# Supply_5V_ISOL.net
KiCad netlist of a schematic drawn in Altium Designer
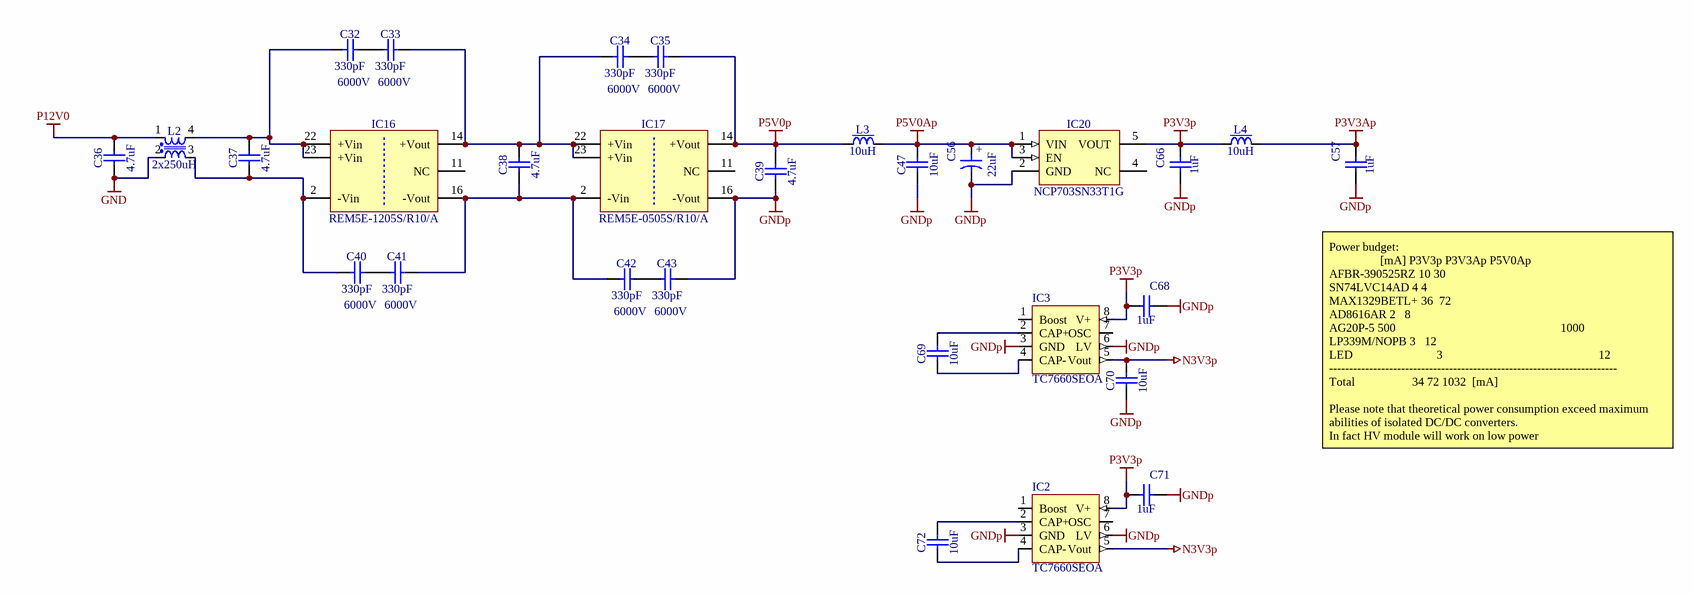
[diagram p0: Supply_5V_ISOL.SchDoc]

(export (version "E")
  (design (tool "Eeschema 10.0.6"))
  (components
    (comp (ref "C32")
      (value "330pF")
      (footprint "CAPC4620X220N")
      (description "Non-polarised capacitor")
      (fields
        (field (name "PART NUMBER") "CC1808_330pF_6000V_10%_X7R_VISHAY_HV")
        (field (name "VOLTAGE") "6000V")
        (field (name "TOLERANCE") "±10%")
        (field (name "AUTHOR") "CERN DEM HF")
      )
      (libsource (lib "Capacitors") (part "Capacitor - non polarized"))
    )
    (comp (ref "C33")
      (value "330pF")
      (footprint "CAPC4620X220N")
      (description "Non-polarised capacitor")
      (fields
        (field (name "PART NUMBER") "CC1808_330pF_6000V_10%_X7R_VISHAY_HV")
        (field (name "VOLTAGE") "6000V")
        (field (name "TOLERANCE") "±10%")
        (field (name "AUTHOR") "CERN DEM HF")
      )
      (libsource (lib "Capacitors") (part "Capacitor - non polarized"))
    )
    (comp (ref "C34")
      (value "330pF")
      (footprint "CAPC4620X220N")
      (description "Non-polarised capacitor")
      (fields
        (field (name "PART NUMBER") "CC1808_330pF_6000V_10%_X7R_VISHAY_HV")
        (field (name "VOLTAGE") "6000V")
        (field (name "TOLERANCE") "±10%")
        (field (name "AUTHOR") "CERN DEM HF")
      )
      (libsource (lib "Capacitors") (part "Capacitor - non polarized"))
    )
    (comp (ref "C35")
      (value "330pF")
      (footprint "CAPC4620X220N")
      (description "Non-polarised capacitor")
      (fields
        (field (name "PART NUMBER") "CC1808_330pF_6000V_10%_X7R_VISHAY_HV")
        (field (name "VOLTAGE") "6000V")
        (field (name "TOLERANCE") "±10%")
        (field (name "AUTHOR") "CERN DEM HF")
      )
      (libsource (lib "Capacitors") (part "Capacitor - non polarized"))
    )
    (comp (ref "C36")
      (value "4.7uF")
      (footprint "CAPC2012X145N")
      (description "Non-polarised capacitor")
      (fields
        (field (name "PART NUMBER") "CC0805_4.7UF_50V_10%_X7R")
        (field (name "VOLTAGE") "50V")
        (field (name "AUTHOR") "CERN DEM JMW")
      )
      (libsource (lib "Capacitors") (part "Capacitor - non polarized"))
    )
    (comp (ref "C37")
      (value "4.7uF")
      (footprint "CAPC2012X145N")
      (description "Non-polarised capacitor")
      (fields
        (field (name "PART NUMBER") "CC0805_4.7UF_50V_10%_X7R")
        (field (name "VOLTAGE") "50V")
        (field (name "AUTHOR") "CERN DEM JMW")
      )
      (libsource (lib "Capacitors") (part "Capacitor - non polarized"))
    )
    (comp (ref "C38")
      (value "4.7uF")
      (footprint "CAPC2012X145N")
      (description "Non-polarised capacitor")
      (fields
        (field (name "PART NUMBER") "CC0805_4.7UF_50V_10%_X7R")
        (field (name "VOLTAGE") "50V")
        (field (name "AUTHOR") "CERN DEM JMW")
      )
      (libsource (lib "Capacitors") (part "Capacitor - non polarized"))
    )
    (comp (ref "C39")
      (value "4.7uF")
      (footprint "CAPC2012X145N")
      (description "Non-polarised capacitor")
      (fields
        (field (name "PART NUMBER") "CC0805_4.7UF_50V_10%_X7R")
        (field (name "VOLTAGE") "50V")
        (field (name "AUTHOR") "CERN DEM JMW")
      )
      (libsource (lib "Capacitors") (part "Capacitor - non polarized"))
    )
    (comp (ref "C40")
      (value "330pF")
      (footprint "CAPC4620X220N")
      (description "Non-polarised capacitor")
      (fields
        (field (name "PART NUMBER") "CC1808_330pF_6000V_10%_X7R_VISHAY_HV")
        (field (name "VOLTAGE") "6000V")
        (field (name "TOLERANCE") "±10%")
        (field (name "AUTHOR") "CERN DEM HF")
      )
      (libsource (lib "Capacitors") (part "Capacitor - non polarized"))
    )
    (comp (ref "C41")
      (value "330pF")
      (footprint "CAPC4620X220N")
      (description "Non-polarised capacitor")
      (fields
        (field (name "PART NUMBER") "CC1808_330pF_6000V_10%_X7R_VISHAY_HV")
        (field (name "VOLTAGE") "6000V")
        (field (name "TOLERANCE") "±10%")
        (field (name "AUTHOR") "CERN DEM HF")
      )
      (libsource (lib "Capacitors") (part "Capacitor - non polarized"))
    )
    (comp (ref "C42")
      (value "330pF")
      (footprint "CAPC4620X220N")
      (description "Non-polarised capacitor")
      (fields
        (field (name "PART NUMBER") "CC1808_330pF_6000V_10%_X7R_VISHAY_HV")
        (field (name "VOLTAGE") "6000V")
        (field (name "TOLERANCE") "±10%")
        (field (name "AUTHOR") "CERN DEM HF")
      )
      (libsource (lib "Capacitors") (part "Capacitor - non polarized"))
    )
    (comp (ref "C43")
      (value "330pF")
      (footprint "CAPC4620X220N")
      (description "Non-polarised capacitor")
      (fields
        (field (name "PART NUMBER") "CC1808_330pF_6000V_10%_X7R_VISHAY_HV")
        (field (name "VOLTAGE") "6000V")
        (field (name "TOLERANCE") "±10%")
        (field (name "AUTHOR") "CERN DEM HF")
      )
      (libsource (lib "Capacitors") (part "Capacitor - non polarized"))
    )
    (comp (ref "C47")
      (value "10uF")
      (footprint "CAPC1608X80N")
      (description "Non-polarised capacitor")
      (fields
        (field (name "PART NUMBER") "CC0603_10UF_16V_20%_X5R")
        (field (name "VOLTAGE") "16V")
        (field (name "AUTHOR") "CERN DEM MR")
      )
      (libsource (lib "Capacitors") (part "Capacitor - non polarized"))
    )
    (comp (ref "C56")
      (value "22uF")
      (footprint "CAPMP3528X210N")
      (description "Polarised capacitor")
      (fields
        (field (name "PART NUMBER") "CTE3528-21_22UF_20V_10%")
        (field (name "VOLTAGE") "20V")
        (field (name "AUTHOR") "CERN DEM JLC")
      )
      (libsource (lib "Capacitors") (part "Capacitor - polarized"))
    )
    (comp (ref "C57")
      (value "1uF")
      (footprint "CAPC1005X55N")
      (description "Non-polarised capacitor")
      (fields
        (field (name "PART NUMBER") "CC0402_1UF_16V_10%_X5R")
        (field (name "VOLTAGE") "16V")
        (field (name "AUTHOR") "CERN DEM JLC")
      )
      (libsource (lib "Capacitors") (part "Capacitor - non polarized"))
    )
    (comp (ref "C66")
      (value "1uF")
      (footprint "CAPC1005X55N")
      (description "Non-polarised capacitor")
      (fields
        (field (name "PART NUMBER") "CC0402_1UF_16V_10%_X5R")
        (field (name "VOLTAGE") "16V")
        (field (name "AUTHOR") "CERN DEM JLC")
      )
      (libsource (lib "Capacitors") (part "Capacitor - non polarized"))
    )
    (comp (ref "C68")
      (value "1uF")
      (footprint "CAPC1005X55N")
      (description "Non-polarised capacitor")
      (fields
        (field (name "PART NUMBER") "CC0402_1UF_16V_10%_X5R")
        (field (name "VOLTAGE") "16V")
        (field (name "AUTHOR") "CERN DEM JLC")
      )
      (libsource (lib "Capacitors") (part "Capacitor - non polarized"))
    )
    (comp (ref "C69")
      (value "10uF")
      (footprint "CAPC1608X80N")
      (description "Non-polarised capacitor")
      (fields
        (field (name "PART NUMBER") "CC0603_10UF_16V_20%_X5R")
        (field (name "VOLTAGE") "16V")
        (field (name "AUTHOR") "CERN DEM MR")
      )
      (libsource (lib "Capacitors") (part "Capacitor - non polarized"))
    )
    (comp (ref "C70")
      (value "10uF")
      (footprint "CAPC1608X80N")
      (description "Non-polarised capacitor")
      (fields
        (field (name "PART NUMBER") "CC0603_10UF_16V_20%_X5R")
        (field (name "VOLTAGE") "16V")
        (field (name "AUTHOR") "CERN DEM MR")
      )
      (libsource (lib "Capacitors") (part "Capacitor - non polarized"))
    )
    (comp (ref "C71")
      (value "1uF")
      (footprint "CAPC1005X55N")
      (description "Non-polarised capacitor")
      (fields
        (field (name "PART NUMBER") "CC0402_1UF_16V_10%_X5R")
        (field (name "VOLTAGE") "16V")
        (field (name "AUTHOR") "CERN DEM JLC")
      )
      (libsource (lib "Capacitors") (part "Capacitor - non polarized"))
    )
    (comp (ref "C72")
      (value "10uF")
      (footprint "CAPC1608X80N")
      (description "Non-polarised capacitor")
      (fields
        (field (name "PART NUMBER") "CC0603_10UF_16V_20%_X5R")
        (field (name "VOLTAGE") "16V")
        (field (name "AUTHOR") "CERN DEM MR")
      )
      (libsource (lib "Capacitors") (part "Capacitor - non polarized"))
    )
    (comp (ref "IC2")
      (value "TC7660SEOA")
      (footprint "SO-8")
      (description "20mA PUMP DC-TO-DC VOLTAGE CONVERTER")
      (libsource (lib "LIBRARY_SCH") (part "PM_TC7660"))
    )
    (comp (ref "IC3")
      (value "TC7660SEOA")
      (footprint "SO-8")
      (description "20mA PUMP DC-TO-DC VOLTAGE CONVERTER")
      (libsource (lib "LIBRARY_SCH") (part "PM_TC7660"))
    )
    (comp (ref "IC16")
      (value "REM5E-1205S/R10/A")
      (footprint "DCDC_RECOM_REM5E-XXXXS")
      (description "RECOM, RP Series, Single Output DCDC Converter")
      (fields (field (name "MANUFACTURER") "RECOM") (field (name "AUTHOR") "CERN DEM HF"))
      (libsource (lib "ICs And Semiconductors") (part "DCDC_RECOM_REM5E-XXXXS"))
    )
    (comp (ref "IC17")
      (value "REM5E-0505S/R10/A")
      (footprint "DCDC_RECOM_REM5E-XXXXS")
      (description "RECOM, RP Series, Single Output DCDC Converter")
      (fields (field (name "MANUFACTURER") "RECOM") (field (name "AUTHOR") "CERN DEM HF"))
      (libsource (lib "ICs And Semiconductors") (part "DCDC_RECOM_REM5E-XXXXS"))
    )
    (comp (ref "IC20")
      (value "NCP703SN33T1G")
      (footprint "SOT95P275X110-5N")
      (description "3.3V 300mA, Ultra-Low Quiescent Current, IQ 12uA, Ultra-Low Noise, LDO Voltage Regulator")
      (fields (field (name "MANUFACTURER") "ON SEMICONDUCTOR") (field (name "AUTHOR") "CERN DEM JLC"))
      (libsource (lib "ICs And Semiconductors") (part "NCP703SN"))
    )
    (comp (ref "L2")
      (value "2x250uH")
      (footprint "IND_WURTH_WE-SL2")
      (description "Inductor Common Mode")
      (fields
        (field (name "PART NUMBER") "IND_250UH_50%_WURTH_WE-SL2-744224")
        (field (name "POWER") "1.2A")
        (field (name "AUTHOR") "CERN DEM JLC")
      )
      (libsource (lib "Inductors & Transformers") (part "Inductor Common Mode 1Dot-4 2Dot-3"))
    )
    (comp (ref "L3")
      (value "10uH")
      (footprint "IND_BOURNS_PM43")
      (description "Inductor With Core")
      (fields
        (field (name "PART NUMBER") "IND_10UH_20%_BOURNS_PM43")
        (field (name "POWER") "1.15A")
        (field (name "AUTHOR") "CERN DEM JLC")
      )
      (libsource (lib "Inductors & Transformers") (part "Inductor With Magnetic core"))
    )
    (comp (ref "L4")
      (value "10uH")
      (footprint "IND_BOURNS_PM43")
      (description "Inductor With Core")
      (fields
        (field (name "PART NUMBER") "IND_10UH_20%_BOURNS_PM43")
        (field (name "POWER") "1.15A")
        (field (name "AUTHOR") "CERN DEM JLC")
      )
      (libsource (lib "Inductors & Transformers") (part "Inductor With Magnetic core"))
    )
  )
  (nets
    (net (code "1") (name "GND") (class "Default")
      (node (ref "C36") (pin "1") (pinfunction "1_1") (pintype "passive"))
      (node (ref "L2") (pin "2") (pinfunction "2_2") (pintype "passive"))
    )
    (net (code "2") (name "GNDp") (class "Default")
      (node (ref "C39") (pin "1") (pinfunction "1_1") (pintype "passive"))
      (node (ref "C43") (pin "2") (pinfunction "2_2") (pintype "passive"))
      (node (ref "C47") (pin "1") (pinfunction "1_1") (pintype "passive"))
      (node (ref "C56") (pin "2") (pinfunction "2_2") (pintype "passive"))
      (node (ref "C57") (pin "1") (pinfunction "1_1") (pintype "passive"))
      (node (ref "C66") (pin "1") (pinfunction "1_1") (pintype "passive"))
      (node (ref "C68") (pin "2") (pinfunction "2_2") (pintype "passive"))
      (node (ref "C70") (pin "1") (pinfunction "1_1") (pintype "passive"))
      (node (ref "C71") (pin "2") (pinfunction "2_2") (pintype "passive"))
      (node (ref "IC17") (pin "16") (pinfunction "-Vout_16") (pintype "power_in"))
      (node (ref "IC2") (pin "3") (pinfunction "GND_3") (pintype "power_in"))
      (node (ref "IC2") (pin "6") (pinfunction "LV_6") (pintype "output"))
      (node (ref "IC20") (pin "2") (pinfunction "GND_2") (pintype "power_in"))
      (node (ref "IC3") (pin "3") (pinfunction "GND_3") (pintype "power_in"))
      (node (ref "IC3") (pin "6") (pinfunction "LV_6") (pintype "output"))
    )
    (net (code "3") (name "N3V3p") (class "Default")
      (node (ref "C70") (pin "2") (pinfunction "2_2") (pintype "passive"))
      (node (ref "IC2") (pin "5") (pinfunction "Vout_5") (pintype "output"))
      (node (ref "IC3") (pin "5") (pinfunction "Vout_5") (pintype "output"))
    )
    (net (code "4") (name "Net-(C32-Pad1)") (class "Default")
      (node (ref "C32") (pin "1") (pinfunction "1_1") (pintype "passive"))
      (node (ref "C37") (pin "2") (pinfunction "2_2") (pintype "passive"))
      (node (ref "IC16") (pin "22") (pinfunction "+Vin_22") (pintype "power_in"))
      (node (ref "IC16") (pin "23") (pinfunction "+Vin_23") (pintype "power_in"))
      (node (ref "L2") (pin "4") (pinfunction "4_4") (pintype "passive"))
    )
    (net (code "5") (name "Net-(C32-Pad2)") (class "Default")
      (node (ref "C32") (pin "2") (pinfunction "2_2") (pintype "passive"))
      (node (ref "C33") (pin "1") (pinfunction "1_1") (pintype "passive"))
    )
    (net (code "6") (name "Net-(C34-Pad2)") (class "Default")
      (node (ref "C34") (pin "2") (pinfunction "2_2") (pintype "passive"))
      (node (ref "C35") (pin "1") (pinfunction "1_1") (pintype "passive"))
    )
    (net (code "7") (name "Net-(C40-Pad2)") (class "Default")
      (node (ref "C40") (pin "2") (pinfunction "2_2") (pintype "passive"))
      (node (ref "C41") (pin "1") (pinfunction "1_1") (pintype "passive"))
    )
    (net (code "8") (name "Net-(C42-Pad2)") (class "Default")
      (node (ref "C42") (pin "2") (pinfunction "2_2") (pintype "passive"))
      (node (ref "C43") (pin "1") (pinfunction "1_1") (pintype "passive"))
    )
    (net (code "9") (name "Net-(IC2-CAP+)") (class "Default")
      (node (ref "C72") (pin "2") (pinfunction "2_2") (pintype "passive"))
      (node (ref "IC2") (pin "2") (pinfunction "CAP+_2") (pintype "passive"))
    )
    (net (code "10") (name "Net-(IC2-CAP-)") (class "Default")
      (node (ref "C72") (pin "1") (pinfunction "1_1") (pintype "passive"))
      (node (ref "IC2") (pin "4") (pinfunction "CAP-_4") (pintype "power_in"))
    )
    (net (code "11") (name "Net-(IC3-CAP+)") (class "Default")
      (node (ref "C69") (pin "2") (pinfunction "2_2") (pintype "passive"))
      (node (ref "IC3") (pin "2") (pinfunction "CAP+_2") (pintype "passive"))
    )
    (net (code "12") (name "Net-(IC3-CAP-)") (class "Default")
      (node (ref "C69") (pin "1") (pinfunction "1_1") (pintype "passive"))
      (node (ref "IC3") (pin "4") (pinfunction "CAP-_4") (pintype "power_in"))
    )
    (net (code "13") (name "Net-(IC16-+Vout)") (class "Default")
      (node (ref "C33") (pin "2") (pinfunction "2_2") (pintype "passive"))
      (node (ref "C34") (pin "1") (pinfunction "1_1") (pintype "passive"))
      (node (ref "C38") (pin "2") (pinfunction "2_2") (pintype "passive"))
      (node (ref "IC16") (pin "14") (pinfunction "+Vout_14") (pintype "power_in"))
      (node (ref "IC17") (pin "22") (pinfunction "+Vin_22") (pintype "power_in"))
      (node (ref "IC17") (pin "23") (pinfunction "+Vin_23") (pintype "power_in"))
    )
    (net (code "14") (name "Net-(IC16--Vin)") (class "Default")
      (node (ref "C37") (pin "1") (pinfunction "1_1") (pintype "passive"))
      (node (ref "C40") (pin "1") (pinfunction "1_1") (pintype "passive"))
      (node (ref "IC16") (pin "2") (pinfunction "-Vin_2") (pintype "power_in"))
      (node (ref "L2") (pin "3") (pinfunction "3_3") (pintype "passive"))
    )
    (net (code "15") (name "Net-(IC16--Vout)") (class "Default")
      (node (ref "C38") (pin "1") (pinfunction "1_1") (pintype "passive"))
      (node (ref "C41") (pin "2") (pinfunction "2_2") (pintype "passive"))
      (node (ref "C42") (pin "1") (pinfunction "1_1") (pintype "passive"))
      (node (ref "IC16") (pin "16") (pinfunction "-Vout_16") (pintype "power_in"))
      (node (ref "IC17") (pin "2") (pinfunction "-Vin_2") (pintype "power_in"))
    )
    (net (code "16") (name "P3V3Ap") (class "Default")
      (node (ref "C57") (pin "2") (pinfunction "2_2") (pintype "passive"))
      (node (ref "L4") (pin "2") (pinfunction "2_2") (pintype "passive"))
    )
    (net (code "17") (name "P3V3p") (class "Default")
      (node (ref "C66") (pin "2") (pinfunction "2_2") (pintype "passive"))
      (node (ref "C68") (pin "1") (pinfunction "1_1") (pintype "passive"))
      (node (ref "C71") (pin "1") (pinfunction "1_1") (pintype "passive"))
      (node (ref "IC2") (pin "8") (pinfunction "V+_8") (pintype "input"))
      (node (ref "IC20") (pin "5") (pinfunction "VOUT_5") (pintype "power_in"))
      (node (ref "IC3") (pin "8") (pinfunction "V+_8") (pintype "input"))
      (node (ref "L4") (pin "1") (pinfunction "1_1") (pintype "passive"))
    )
    (net (code "18") (name "P5V0Ap") (class "Default")
      (node (ref "C47") (pin "2") (pinfunction "2_2") (pintype "passive"))
      (node (ref "C56") (pin "1") (pinfunction "1_1") (pintype "passive"))
      (node (ref "IC20") (pin "1") (pinfunction "VIN_1") (pintype "input"))
      (node (ref "IC20") (pin "3") (pinfunction "EN_3") (pintype "input"))
      (node (ref "L3") (pin "2") (pinfunction "2_2") (pintype "passive"))
    )
    (net (code "19") (name "P5V0p") (class "Default")
      (node (ref "C35") (pin "2") (pinfunction "2_2") (pintype "passive"))
      (node (ref "C39") (pin "2") (pinfunction "2_2") (pintype "passive"))
      (node (ref "IC17") (pin "14") (pinfunction "+Vout_14") (pintype "power_in"))
      (node (ref "L3") (pin "1") (pinfunction "1_1") (pintype "passive"))
    )
    (net (code "20") (name "P12V0") (class "Default")
      (node (ref "C36") (pin "2") (pinfunction "2_2") (pintype "passive"))
      (node (ref "L2") (pin "1") (pinfunction "1_1") (pintype "passive"))
    )
    (net (code "21") (name "unconnected-(IC2-Boost-Pad1)") (class "Default")
      (node (ref "IC2") (pin "1") (pinfunction "Boost_1") (pintype "passive"))
    )
    (net (code "22") (name "unconnected-(IC2-OSC-Pad7)") (class "Default")
      (node (ref "IC2") (pin "7") (pinfunction "OSC_7") (pintype "passive"))
    )
    (net (code "23") (name "unconnected-(IC3-Boost-Pad1)") (class "Default")
      (node (ref "IC3") (pin "1") (pinfunction "Boost_1") (pintype "passive"))
    )
    (net (code "24") (name "unconnected-(IC3-OSC-Pad7)") (class "Default")
      (node (ref "IC3") (pin "7") (pinfunction "OSC_7") (pintype "passive"))
    )
    (net (code "25") (name "unconnected-(IC16-NC-Pad11)") (class "Default")
      (node (ref "IC16") (pin "11") (pinfunction "NC_11") (pintype "power_in"))
    )
    (net (code "26") (name "unconnected-(IC17-NC-Pad11)") (class "Default")
      (node (ref "IC17") (pin "11") (pinfunction "NC_11") (pintype "power_in"))
    )
    (net (code "27") (name "unconnected-(IC20-NC-Pad4)") (class "Default")
      (node (ref "IC20") (pin "4") (pinfunction "NC_4") (pintype "passive"))
    )
  )
)
